# odometry_robot_pcb_sheme.net
KiCad netlist of a schematic drawn in EAGLE
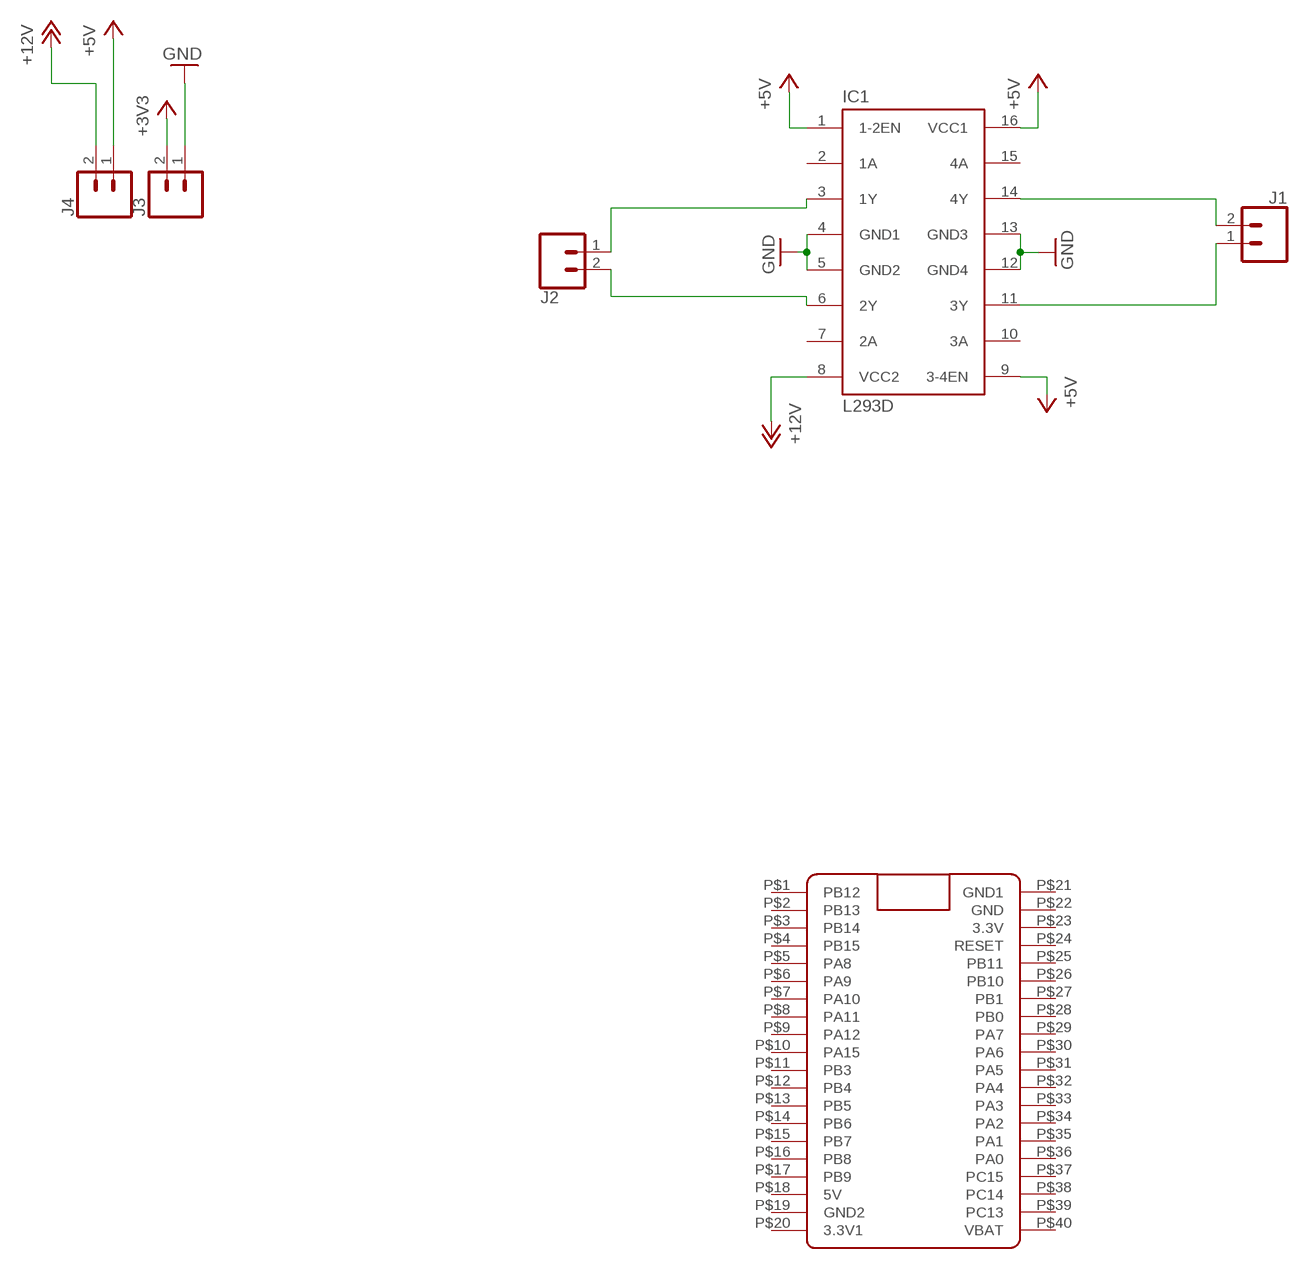
[diagram p0: schematic, sheet 1]

(export (version "E")
  (design (tool "Eeschema 10.0.6"))
  (components
    (comp (ref "IC1")
      (value "L293D")
      (footprint "eagle-import:DIL16")
      (libsource (lib "eagle-import") (part "L293D"))
    )
    (comp (ref "J1")
      (value "CONN_025MM")
      (footprint "eagle-import:SCREWTERMINAL-5MM-2")
      (libsource (lib "eagle-import") (part "CONN_025MM"))
    )
    (comp (ref "J2")
      (value "CONN_025MM")
      (footprint "eagle-import:SCREWTERMINAL-5MM-2")
      (libsource (lib "eagle-import") (part "CONN_025MM"))
    )
    (comp (ref "J3")
      (value "CONN_025MM")
      (footprint "eagle-import:SCREWTERMINAL-5MM-2")
      (libsource (lib "eagle-import") (part "CONN_025MM"))
    )
    (comp (ref "J4")
      (value "CONN_025MM")
      (footprint "eagle-import:SCREWTERMINAL-5MM-2")
      (libsource (lib "eagle-import") (part "CONN_025MM"))
    )
    (comp (ref "U$1")
      (value "BLUE_PILLADVANCED")
      (footprint "eagle-import:BLUE_PILL_ADV")
      (libsource (lib "eagle-import") (part "BLUE_PILLADVANCED"))
    )
  )
  (nets
    (net (code "1") (name "+3V3") (class "Default")
      (node (ref "J3") (pin "2") (pinfunction "2_2") (pintype "passive"))
    )
    (net (code "2") (name "+5V") (class "Default")
      (node (ref "IC1") (pin "1") (pinfunction "1-2EN_1") (pintype "input"))
      (node (ref "IC1") (pin "16") (pinfunction "VCC1_16") (pintype "power_in"))
      (node (ref "IC1") (pin "9") (pinfunction "3-4EN_9") (pintype "input"))
      (node (ref "J4") (pin "1") (pinfunction "1_1") (pintype "passive"))
    )
    (net (code "3") (name "+12V") (class "Default")
      (node (ref "IC1") (pin "8") (pinfunction "VCC2_8") (pintype "power_in"))
      (node (ref "J4") (pin "2") (pinfunction "2_2") (pintype "passive"))
    )
    (net (code "4") (name "/GND1") (class "Default")
      (node (ref "U$1") (pin "P$21") (pinfunction "GND1_P$21") (pintype "power_in"))
    )
    (net (code "5") (name "GND") (class "Default")
      (node (ref "IC1") (pin "12") (pinfunction "GND4_12") (pintype "power_in"))
      (node (ref "IC1") (pin "13") (pinfunction "GND3_13") (pintype "power_in"))
      (node (ref "IC1") (pin "4") (pinfunction "GND1_4") (pintype "power_in"))
      (node (ref "IC1") (pin "5") (pinfunction "GND2_5") (pintype "power_in"))
      (node (ref "J3") (pin "1") (pinfunction "1_1") (pintype "passive"))
    )
    (net (code "6") (name "Net-(IC1-1Y)") (class "Default")
      (node (ref "IC1") (pin "3") (pinfunction "1Y_3") (pintype "output"))
      (node (ref "J2") (pin "1") (pinfunction "1_1") (pintype "passive"))
    )
    (net (code "7") (name "Net-(IC1-2Y)") (class "Default")
      (node (ref "IC1") (pin "6") (pinfunction "2Y_6") (pintype "output"))
      (node (ref "J2") (pin "2") (pinfunction "2_2") (pintype "passive"))
    )
    (net (code "8") (name "Net-(IC1-3Y)") (class "Default")
      (node (ref "IC1") (pin "11") (pinfunction "3Y_11") (pintype "output"))
      (node (ref "J1") (pin "1") (pinfunction "1_1") (pintype "passive"))
    )
    (net (code "9") (name "Net-(IC1-4Y)") (class "Default")
      (node (ref "IC1") (pin "14") (pinfunction "4Y_14") (pintype "output"))
      (node (ref "J1") (pin "2") (pinfunction "2_2") (pintype "passive"))
    )
    (net (code "10") (name "unconnected-(IC1-1A-Pad2)") (class "Default")
      (node (ref "IC1") (pin "2") (pinfunction "1A_2") (pintype "input"))
    )
    (net (code "11") (name "unconnected-(IC1-2A-Pad7)") (class "Default")
      (node (ref "IC1") (pin "7") (pinfunction "2A_7") (pintype "input"))
    )
    (net (code "12") (name "unconnected-(IC1-3A-Pad10)") (class "Default")
      (node (ref "IC1") (pin "10") (pinfunction "3A_10") (pintype "input"))
    )
    (net (code "13") (name "unconnected-(IC1-4A-Pad15)") (class "Default")
      (node (ref "IC1") (pin "15") (pinfunction "4A_15") (pintype "input"))
    )
    (net (code "14") (name "unconnected-(U$1-3.3V-PadP$23)") (class "Default")
      (node (ref "U$1") (pin "P$23") (pinfunction "3.3V_P$23") (pintype "bidirectional"))
    )
    (net (code "15") (name "unconnected-(U$1-3.3V1-PadP$20)") (class "Default")
      (node (ref "U$1") (pin "P$20") (pinfunction "3.3V1_P$20") (pintype "bidirectional"))
    )
    (net (code "16") (name "unconnected-(U$1-5V-PadP$18)") (class "Default")
      (node (ref "U$1") (pin "P$18") (pinfunction "5V_P$18") (pintype "bidirectional"))
    )
    (net (code "17") (name "unconnected-(U$1-GND-PadP$22)") (class "Default")
      (node (ref "U$1") (pin "P$22") (pinfunction "GND_P$22") (pintype "bidirectional"))
    )
    (net (code "18") (name "unconnected-(U$1-GND2-PadP$19)") (class "Default")
      (node (ref "U$1") (pin "P$19") (pinfunction "GND2_P$19") (pintype "bidirectional"))
    )
    (net (code "19") (name "unconnected-(U$1-PA0-PadP$36)") (class "Default")
      (node (ref "U$1") (pin "P$36") (pinfunction "PA0_P$36") (pintype "bidirectional"))
    )
    (net (code "20") (name "unconnected-(U$1-PA1-PadP$35)") (class "Default")
      (node (ref "U$1") (pin "P$35") (pinfunction "PA1_P$35") (pintype "bidirectional"))
    )
    (net (code "21") (name "unconnected-(U$1-PA2-PadP$34)") (class "Default")
      (node (ref "U$1") (pin "P$34") (pinfunction "PA2_P$34") (pintype "bidirectional"))
    )
    (net (code "22") (name "unconnected-(U$1-PA3-PadP$33)") (class "Default")
      (node (ref "U$1") (pin "P$33") (pinfunction "PA3_P$33") (pintype "bidirectional"))
    )
    (net (code "23") (name "unconnected-(U$1-PA4-PadP$32)") (class "Default")
      (node (ref "U$1") (pin "P$32") (pinfunction "PA4_P$32") (pintype "bidirectional"))
    )
    (net (code "24") (name "unconnected-(U$1-PA5-PadP$31)") (class "Default")
      (node (ref "U$1") (pin "P$31") (pinfunction "PA5_P$31") (pintype "bidirectional"))
    )
    (net (code "25") (name "unconnected-(U$1-PA6-PadP$30)") (class "Default")
      (node (ref "U$1") (pin "P$30") (pinfunction "PA6_P$30") (pintype "bidirectional"))
    )
    (net (code "26") (name "unconnected-(U$1-PA7-PadP$29)") (class "Default")
      (node (ref "U$1") (pin "P$29") (pinfunction "PA7_P$29") (pintype "bidirectional"))
    )
    (net (code "27") (name "unconnected-(U$1-PA8-PadP$5)") (class "Default")
      (node (ref "U$1") (pin "P$5") (pinfunction "PA8_P$5") (pintype "bidirectional"))
    )
    (net (code "28") (name "unconnected-(U$1-PA9-PadP$6)") (class "Default")
      (node (ref "U$1") (pin "P$6") (pinfunction "PA9_P$6") (pintype "bidirectional"))
    )
    (net (code "29") (name "unconnected-(U$1-PA10-PadP$7)") (class "Default")
      (node (ref "U$1") (pin "P$7") (pinfunction "PA10_P$7") (pintype "bidirectional"))
    )
    (net (code "30") (name "unconnected-(U$1-PA11-PadP$8)") (class "Default")
      (node (ref "U$1") (pin "P$8") (pinfunction "PA11_P$8") (pintype "bidirectional"))
    )
    (net (code "31") (name "unconnected-(U$1-PA12-PadP$9)") (class "Default")
      (node (ref "U$1") (pin "P$9") (pinfunction "PA12_P$9") (pintype "bidirectional"))
    )
    (net (code "32") (name "unconnected-(U$1-PA15-PadP$10)") (class "Default")
      (node (ref "U$1") (pin "P$10") (pinfunction "PA15_P$10") (pintype "bidirectional"))
    )
    (net (code "33") (name "unconnected-(U$1-PB0-PadP$28)") (class "Default")
      (node (ref "U$1") (pin "P$28") (pinfunction "PB0_P$28") (pintype "bidirectional"))
    )
    (net (code "34") (name "unconnected-(U$1-PB1-PadP$27)") (class "Default")
      (node (ref "U$1") (pin "P$27") (pinfunction "PB1_P$27") (pintype "bidirectional"))
    )
    (net (code "35") (name "unconnected-(U$1-PB3-PadP$11)") (class "Default")
      (node (ref "U$1") (pin "P$11") (pinfunction "PB3_P$11") (pintype "bidirectional"))
    )
    (net (code "36") (name "unconnected-(U$1-PB4-PadP$12)") (class "Default")
      (node (ref "U$1") (pin "P$12") (pinfunction "PB4_P$12") (pintype "bidirectional"))
    )
    (net (code "37") (name "unconnected-(U$1-PB5-PadP$13)") (class "Default")
      (node (ref "U$1") (pin "P$13") (pinfunction "PB5_P$13") (pintype "bidirectional"))
    )
    (net (code "38") (name "unconnected-(U$1-PB6-PadP$14)") (class "Default")
      (node (ref "U$1") (pin "P$14") (pinfunction "PB6_P$14") (pintype "bidirectional"))
    )
    (net (code "39") (name "unconnected-(U$1-PB7-PadP$15)") (class "Default")
      (node (ref "U$1") (pin "P$15") (pinfunction "PB7_P$15") (pintype "bidirectional"))
    )
    (net (code "40") (name "unconnected-(U$1-PB8-PadP$16)") (class "Default")
      (node (ref "U$1") (pin "P$16") (pinfunction "PB8_P$16") (pintype "bidirectional"))
    )
    (net (code "41") (name "unconnected-(U$1-PB9-PadP$17)") (class "Default")
      (node (ref "U$1") (pin "P$17") (pinfunction "PB9_P$17") (pintype "bidirectional"))
    )
    (net (code "42") (name "unconnected-(U$1-PB10-PadP$26)") (class "Default")
      (node (ref "U$1") (pin "P$26") (pinfunction "PB10_P$26") (pintype "bidirectional"))
    )
    (net (code "43") (name "unconnected-(U$1-PB11-PadP$25)") (class "Default")
      (node (ref "U$1") (pin "P$25") (pinfunction "PB11_P$25") (pintype "bidirectional"))
    )
    (net (code "44") (name "unconnected-(U$1-PB12-PadP$1)") (class "Default")
      (node (ref "U$1") (pin "P$1") (pinfunction "PB12_P$1") (pintype "bidirectional"))
    )
    (net (code "45") (name "unconnected-(U$1-PB13-PadP$2)") (class "Default")
      (node (ref "U$1") (pin "P$2") (pinfunction "PB13_P$2") (pintype "bidirectional"))
    )
    (net (code "46") (name "unconnected-(U$1-PB14-PadP$3)") (class "Default")
      (node (ref "U$1") (pin "P$3") (pinfunction "PB14_P$3") (pintype "bidirectional"))
    )
    (net (code "47") (name "unconnected-(U$1-PB15-PadP$4)") (class "Default")
      (node (ref "U$1") (pin "P$4") (pinfunction "PB15_P$4") (pintype "bidirectional"))
    )
    (net (code "48") (name "unconnected-(U$1-PC13-PadP$39)") (class "Default")
      (node (ref "U$1") (pin "P$39") (pinfunction "PC13_P$39") (pintype "bidirectional"))
    )
    (net (code "49") (name "unconnected-(U$1-PC14-PadP$38)") (class "Default")
      (node (ref "U$1") (pin "P$38") (pinfunction "PC14_P$38") (pintype "bidirectional"))
    )
    (net (code "50") (name "unconnected-(U$1-PC15-PadP$37)") (class "Default")
      (node (ref "U$1") (pin "P$37") (pinfunction "PC15_P$37") (pintype "bidirectional"))
    )
    (net (code "51") (name "unconnected-(U$1-RESET-PadP$24)") (class "Default")
      (node (ref "U$1") (pin "P$24") (pinfunction "RESET_P$24") (pintype "bidirectional"))
    )
    (net (code "52") (name "unconnected-(U$1-VBAT-PadP$40)") (class "Default")
      (node (ref "U$1") (pin "P$40") (pinfunction "VBAT_P$40") (pintype "bidirectional"))
    )
  )
)
